# FascinationMachine.net
KiCad netlist of a schematic drawn in EAGLE
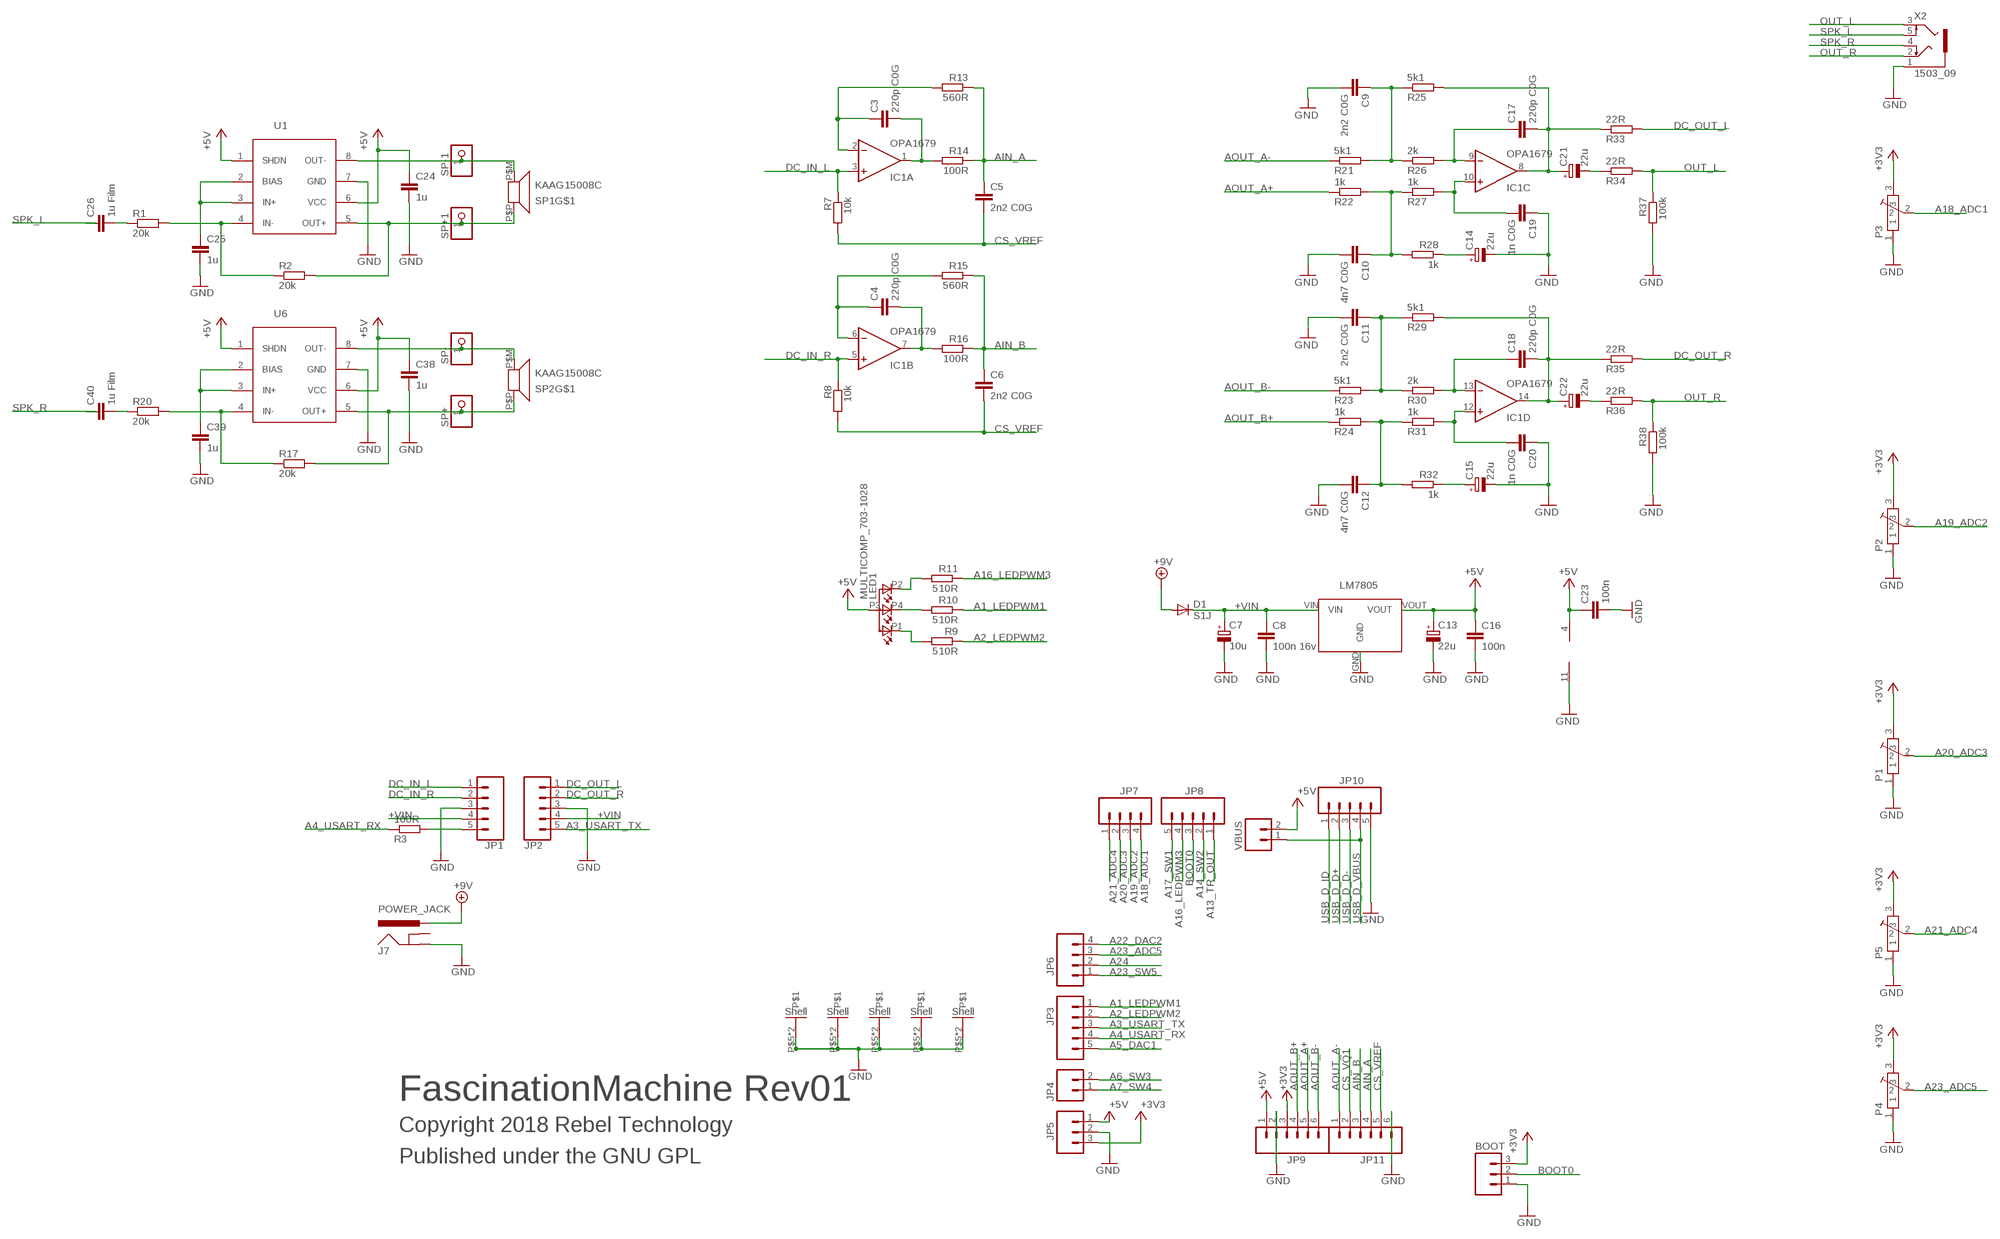
[diagram p0: schematic, sheet 1]

(export (version "E")
  (design (tool "Eeschema 10.0.6"))
  (components
    (comp (ref "BOOT")
      (value "M03PTH")
      (footprint "eagle-import:1X03")
      (libsource (lib "eagle-import") (part "M03PTH"))
    )
    (comp (ref "C3")
      (value "220p C0G")
      (footprint "eagle-import:C0603")
      (libsource (lib "eagle-import") (part "resistor_C-EUC0603"))
    )
    (comp (ref "C4")
      (value "220p C0G")
      (footprint "eagle-import:C0603")
      (libsource (lib "eagle-import") (part "resistor_C-EUC0603"))
    )
    (comp (ref "C5")
      (value "2n2 C0G")
      (footprint "eagle-import:C0603")
      (libsource (lib "eagle-import") (part "resistor_C-EUC0603"))
    )
    (comp (ref "C6")
      (value "2n2 C0G")
      (footprint "eagle-import:C0603")
      (libsource (lib "eagle-import") (part "resistor_C-EUC0603"))
    )
    (comp (ref "C7")
      (value "10u")
      (footprint "eagle-import:153CLV-0405")
      (libsource (lib "eagle-import") (part "CPOL-EU153CLV-0405"))
    )
    (comp (ref "C8")
      (value "100n 16v")
      (footprint "eagle-import:C0603")
      (libsource (lib "eagle-import") (part "C-EUC0603"))
    )
    (comp (ref "C9")
      (value "2n2 C0G")
      (footprint "eagle-import:C0603")
      (libsource (lib "eagle-import") (part "resistor_C-EUC0603"))
    )
    (comp (ref "C10")
      (value "4n7 C0G")
      (footprint "eagle-import:C0603")
      (libsource (lib "eagle-import") (part "resistor_C-EUC0603"))
    )
    (comp (ref "C11")
      (value "2n2 C0G")
      (footprint "eagle-import:C0603")
      (libsource (lib "eagle-import") (part "resistor_C-EUC0603"))
    )
    (comp (ref "C12")
      (value "4n7 C0G")
      (footprint "eagle-import:C0603")
      (libsource (lib "eagle-import") (part "resistor_C-EUC0603"))
    )
    (comp (ref "C13")
      (value "22u")
      (footprint "eagle-import:CPOL-5")
      (libsource (lib "eagle-import") (part "CPOL-EU153CLV-0505"))
    )
    (comp (ref "C14")
      (value "22u")
      (footprint "eagle-import:CPOL-5")
      (libsource (lib "eagle-import") (part "CPOL-EU153CLV-0505"))
    )
    (comp (ref "C15")
      (value "22u")
      (footprint "eagle-import:CPOL-5")
      (libsource (lib "eagle-import") (part "CPOL-EU153CLV-0505"))
    )
    (comp (ref "C16")
      (value "100n")
      (footprint "eagle-import:C0603")
      (libsource (lib "eagle-import") (part "C-EUC0603"))
    )
    (comp (ref "C17")
      (value "220p C0G")
      (footprint "eagle-import:C0603")
      (libsource (lib "eagle-import") (part "resistor_C-EUC0603"))
    )
    (comp (ref "C18")
      (value "220p C0G")
      (footprint "eagle-import:C0603")
      (libsource (lib "eagle-import") (part "resistor_C-EUC0603"))
    )
    (comp (ref "C19")
      (value "1n C0G")
      (footprint "eagle-import:C0603")
      (libsource (lib "eagle-import") (part "resistor_C-EUC0603"))
    )
    (comp (ref "C20")
      (value "1n C0G")
      (footprint "eagle-import:C0603")
      (libsource (lib "eagle-import") (part "resistor_C-EUC0603"))
    )
    (comp (ref "C21")
      (value "22u")
      (footprint "eagle-import:CPOL-5")
      (libsource (lib "eagle-import") (part "CPOL-EU153CLV-0505"))
    )
    (comp (ref "C22")
      (value "22u")
      (footprint "eagle-import:CPOL-5")
      (libsource (lib "eagle-import") (part "CPOL-EU153CLV-0505"))
    )
    (comp (ref "C23")
      (value "100n")
      (footprint "eagle-import:C0603")
      (libsource (lib "eagle-import") (part "resistor_C-EUC0603"))
    )
    (comp (ref "C24")
      (value "1u")
      (footprint "eagle-import:C0603")
      (libsource (lib "eagle-import") (part "resistor_348_C-EUC0603"))
    )
    (comp (ref "C25")
      (value "1u")
      (footprint "eagle-import:C0603")
      (libsource (lib "eagle-import") (part "resistor_348_C-EUC0603"))
    )
    (comp (ref "C26")
      (value "1u Film")
      (footprint "eagle-import:C1210")
      (libsource (lib "eagle-import") (part "C-EUC1210"))
    )
    (comp (ref "C38")
      (value "1u")
      (footprint "eagle-import:C0603")
      (libsource (lib "eagle-import") (part "resistor_348_C-EUC0603"))
    )
    (comp (ref "C39")
      (value "1u")
      (footprint "eagle-import:C0603")
      (libsource (lib "eagle-import") (part "resistor_348_C-EUC0603"))
    )
    (comp (ref "C40")
      (value "1u Film")
      (footprint "eagle-import:C1210")
      (libsource (lib "eagle-import") (part "C-EUC1210"))
    )
    (comp (ref "D1")
      (value "S1J")
      (footprint "eagle-import:SMA-DIODE")
      (libsource (lib "eagle-import") (part "DIODESMA"))
    )
    (comp (ref "IC1")
      (value "OPA1679")
      (footprint "eagle-import:SO14")
      (libsource (lib "eagle-import") (part "LM324D"))
    )
    (comp (ref "J7")
      (value "POWER_JACK")
      (footprint "eagle-import:DC_JACK_SLOT")
      (libsource (lib "eagle-import") (part "POWER_JACK"))
    )
    (comp (ref "JP1")
      (value "CONN_05JST-VERT")
      (footprint "eagle-import:JST-5-PTH-VERT")
      (libsource (lib "eagle-import") (part "CONN_05JST-VERT"))
    )
    (comp (ref "JP2")
      (value "CONN_05JST-VERT")
      (footprint "eagle-import:JST-5-PTH-VERT")
      (libsource (lib "eagle-import") (part "CONN_05JST-VERT"))
    )
    (comp (ref "JP3")
      (value "M05PTH")
      (footprint "eagle-import:1X05")
      (libsource (lib "eagle-import") (part "M05PTH"))
    )
    (comp (ref "JP4")
      (value "M02PTH")
      (footprint "eagle-import:1X02")
      (libsource (lib "eagle-import") (part "M02PTH"))
    )
    (comp (ref "JP5")
      (value "M03PTH")
      (footprint "eagle-import:1X03")
      (libsource (lib "eagle-import") (part "M03PTH"))
    )
    (comp (ref "JP6")
      (value "M04PTH")
      (footprint "eagle-import:1X04")
      (libsource (lib "eagle-import") (part "M04PTH"))
    )
    (comp (ref "JP7")
      (value "M04PTH")
      (footprint "eagle-import:1X04")
      (libsource (lib "eagle-import") (part "M04PTH"))
    )
    (comp (ref "JP8")
      (value "M05PTH")
      (footprint "eagle-import:1X05")
      (libsource (lib "eagle-import") (part "M05PTH"))
    )
    (comp (ref "JP9")
      (value "M06SIP")
      (footprint "eagle-import:1X06")
      (libsource (lib "eagle-import") (part "M06SIP"))
    )
    (comp (ref "JP10")
      (value "M05PTH")
      (footprint "eagle-import:1X05")
      (libsource (lib "eagle-import") (part "M05PTH"))
    )
    (comp (ref "JP11")
      (value "M06SIP")
      (footprint "eagle-import:1X06")
      (libsource (lib "eagle-import") (part "M06SIP"))
    )
    (comp (ref "LED1")
      (value "MULTICOMP_703-1028")
      (footprint "eagle-import:RGB-LED-703-1028")
      (libsource (lib "eagle-import") (part "MULTICOMP_703-1028"))
    )
    (comp (ref "P1")
      (value "POT-ALPS-RK09L1140")
      (footprint "eagle-import:POT-ALPS-RK09L1140")
      (libsource (lib "eagle-import") (part "POT-ALPS-RK09L1140"))
    )
    (comp (ref "P2")
      (value "POT-ALPS-RK09L1140")
      (footprint "eagle-import:POT-ALPS-RK09L1140")
      (libsource (lib "eagle-import") (part "POT-ALPS-RK09L1140"))
    )
    (comp (ref "P3")
      (value "POT-ALPS-RK09L1140")
      (footprint "eagle-import:POT-ALPS-RK09L1140")
      (libsource (lib "eagle-import") (part "POT-ALPS-RK09L1140"))
    )
    (comp (ref "P4")
      (value "POT-ALPS-RK09L1140")
      (footprint "eagle-import:POT-ALPS-RK09L1140")
      (libsource (lib "eagle-import") (part "POT-ALPS-RK09L1140"))
    )
    (comp (ref "P5")
      (value "POT-ALPS-RK09L1140")
      (footprint "eagle-import:POT-ALPS-RK09L1140")
      (libsource (lib "eagle-import") (part "POT-ALPS-RK09L1140"))
    )
    (comp (ref "R1")
      (value "20k")
      (footprint "eagle-import:0603")
      (libsource (lib "eagle-import") (part "R-EU_0603"))
    )
    (comp (ref "R2")
      (value "20k")
      (footprint "eagle-import:0603")
      (libsource (lib "eagle-import") (part "R-EU_0603"))
    )
    (comp (ref "R3")
      (value "100R")
      (footprint "eagle-import:0603")
      (libsource (lib "eagle-import") (part "R-EU_0603"))
    )
    (comp (ref "R7")
      (value "10k")
      (footprint "eagle-import:0603")
      (libsource (lib "eagle-import") (part "R-EU_0603"))
    )
    (comp (ref "R8")
      (value "10k")
      (footprint "eagle-import:0603")
      (libsource (lib "eagle-import") (part "R-EU_0603"))
    )
    (comp (ref "R9")
      (value "510R")
      (footprint "eagle-import:0603")
      (libsource (lib "eagle-import") (part "R-EU_0603"))
    )
    (comp (ref "R10")
      (value "510R")
      (footprint "eagle-import:0603")
      (libsource (lib "eagle-import") (part "R-EU_0603"))
    )
    (comp (ref "R11")
      (value "510R")
      (footprint "eagle-import:0603")
      (libsource (lib "eagle-import") (part "R-EU_0603"))
    )
    (comp (ref "R13")
      (value "560R")
      (footprint "eagle-import:0603")
      (libsource (lib "eagle-import") (part "R-EU_0603"))
    )
    (comp (ref "R14")
      (value "100R")
      (footprint "eagle-import:0603")
      (libsource (lib "eagle-import") (part "R-EU_0603"))
    )
    (comp (ref "R15")
      (value "560R")
      (footprint "eagle-import:0603")
      (libsource (lib "eagle-import") (part "R-EU_0603"))
    )
    (comp (ref "R16")
      (value "100R")
      (footprint "eagle-import:0603")
      (libsource (lib "eagle-import") (part "R-EU_0603"))
    )
    (comp (ref "R17")
      (value "20k")
      (footprint "eagle-import:0603")
      (libsource (lib "eagle-import") (part "R-EU_0603"))
    )
    (comp (ref "R20")
      (value "20k")
      (footprint "eagle-import:0603")
      (libsource (lib "eagle-import") (part "R-EU_0603"))
    )
    (comp (ref "R21")
      (value "5k1")
      (footprint "eagle-import:0603")
      (libsource (lib "eagle-import") (part "R-EU_0603"))
    )
    (comp (ref "R22")
      (value "1k")
      (footprint "eagle-import:0603")
      (libsource (lib "eagle-import") (part "R-EU_0603"))
    )
    (comp (ref "R23")
      (value "5k1")
      (footprint "eagle-import:0603")
      (libsource (lib "eagle-import") (part "R-EU_0603"))
    )
    (comp (ref "R24")
      (value "1k")
      (footprint "eagle-import:0603")
      (libsource (lib "eagle-import") (part "R-EU_0603"))
    )
    (comp (ref "R25")
      (value "5k1")
      (footprint "eagle-import:0603")
      (libsource (lib "eagle-import") (part "R-EU_0603"))
    )
    (comp (ref "R26")
      (value "2k")
      (footprint "eagle-import:0603")
      (libsource (lib "eagle-import") (part "R-EU_0603"))
    )
    (comp (ref "R27")
      (value "1k")
      (footprint "eagle-import:0603")
      (libsource (lib "eagle-import") (part "R-EU_0603"))
    )
    (comp (ref "R28")
      (value "1k")
      (footprint "eagle-import:0603")
      (libsource (lib "eagle-import") (part "R-EU_0603"))
    )
    (comp (ref "R29")
      (value "5k1")
      (footprint "eagle-import:0603")
      (libsource (lib "eagle-import") (part "R-EU_0603"))
    )
    (comp (ref "R30")
      (value "2k")
      (footprint "eagle-import:0603")
      (libsource (lib "eagle-import") (part "R-EU_0603"))
    )
    (comp (ref "R31")
      (value "1k")
      (footprint "eagle-import:0603")
      (libsource (lib "eagle-import") (part "R-EU_0603"))
    )
    (comp (ref "R32")
      (value "1k")
      (footprint "eagle-import:0603")
      (libsource (lib "eagle-import") (part "R-EU_0603"))
    )
    (comp (ref "R33")
      (value "22R")
      (footprint "eagle-import:0603")
      (libsource (lib "eagle-import") (part "R-EU_0603"))
    )
    (comp (ref "R34")
      (value "22R")
      (footprint "eagle-import:0603")
      (libsource (lib "eagle-import") (part "R-EU_0603"))
    )
    (comp (ref "R35")
      (value "22R")
      (footprint "eagle-import:0603")
      (libsource (lib "eagle-import") (part "R-EU_0603"))
    )
    (comp (ref "R36")
      (value "22R")
      (footprint "eagle-import:0603")
      (libsource (lib "eagle-import") (part "R-EU_0603"))
    )
    (comp (ref "R37")
      (value "100k")
      (footprint "eagle-import:0603")
      (libsource (lib "eagle-import") (part "R-EU_0603"))
    )
    (comp (ref "R38")
      (value "100k")
      (footprint "eagle-import:0603")
      (libsource (lib "eagle-import") (part "R-EU_0603"))
    )
    (comp (ref "SP+")
      (value "PINHD-1X1")
      (footprint "eagle-import:1X01")
      (libsource (lib "eagle-import") (part "PINHD-1X1"))
    )
    (comp (ref "SP+1")
      (value "PINHD-1X1")
      (footprint "eagle-import:1X01")
      (libsource (lib "eagle-import") (part "PINHD-1X1"))
    )
    (comp (ref "SP-")
      (value "PINHD-1X1")
      (footprint "eagle-import:1X01")
      (libsource (lib "eagle-import") (part "PINHD-1X1"))
    )
    (comp (ref "SP-1")
      (value "PINHD-1X1")
      (footprint "eagle-import:1X01")
      (libsource (lib "eagle-import") (part "PINHD-1X1"))
    )
    (comp (ref "SP1")
      (value "KAAG15008C")
      (footprint "eagle-import:KAAG15008C")
      (libsource (lib "eagle-import") (part "KAAG15008C"))
    )
    (comp (ref "SP2")
      (value "KAAG15008C")
      (footprint "eagle-import:KAAG15008C")
      (libsource (lib "eagle-import") (part "KAAG15008C"))
    )
    (comp (ref "U1")
      (value "MAX9716")
      (footprint "eagle-import:UMAX8-THERMAL")
      (libsource (lib "eagle-import") (part "MAX9716"))
    )
    (comp (ref "U2")
      (value "LM7805")
      (footprint "eagle-import:REG_S9V11F5")
      (libsource (lib "eagle-import") (part "REG_S9V11F5"))
    )
    (comp (ref "U6")
      (value "MAX9716")
      (footprint "eagle-import:UMAX8-THERMAL")
      (libsource (lib "eagle-import") (part "MAX9716"))
    )
    (comp (ref "VBUS")
      (value "M02PTH")
      (footprint "eagle-import:1X02")
      (libsource (lib "eagle-import") (part "M02PTH"))
    )
    (comp (ref "X2")
      (value "1503_09")
      (footprint "eagle-import:1503_09")
      (libsource (lib "eagle-import") (part "1503_09"))
    )
  )
  (nets
    (net (code "1") (name "+3V3") (class "Default")
      (node (ref "BOOT") (pin "3") (pinfunction "3_3") (pintype "passive"))
      (node (ref "JP5") (pin "3") (pinfunction "3_3") (pintype "passive"))
      (node (ref "JP9") (pin "3") (pinfunction "3_3") (pintype "passive"))
      (node (ref "P1") (pin "3") (pinfunction "3_3") (pintype "bidirectional"))
      (node (ref "P2") (pin "3") (pinfunction "3_3") (pintype "bidirectional"))
      (node (ref "P3") (pin "3") (pinfunction "3_3") (pintype "bidirectional"))
      (node (ref "P4") (pin "3") (pinfunction "3_3") (pintype "bidirectional"))
      (node (ref "P5") (pin "3") (pinfunction "3_3") (pintype "bidirectional"))
    )
    (net (code "2") (name "+5V") (class "Default")
      (node (ref "C13") (pin "+") (pinfunction "+_+") (pintype "passive"))
      (node (ref "C16") (pin "1") (pinfunction "1_1") (pintype "passive"))
      (node (ref "C23") (pin "1") (pinfunction "1_1") (pintype "passive"))
      (node (ref "C24") (pin "1") (pinfunction "1_1") (pintype "passive"))
      (node (ref "C38") (pin "1") (pinfunction "1_1") (pintype "passive"))
      (node (ref "IC1") (pin "4") (pinfunction "V+_4") (pintype "power_in"))
      (node (ref "JP5") (pin "1") (pinfunction "1_1") (pintype "passive"))
      (node (ref "JP9") (pin "1") (pinfunction "1_1") (pintype "passive"))
      (node (ref "LED1") (pin "P3") (pinfunction "A_P3") (pintype "passive"))
      (node (ref "U1") (pin "1") (pinfunction "SHDN_1") (pintype "bidirectional"))
      (node (ref "U1") (pin "6") (pinfunction "VCC_6") (pintype "bidirectional"))
      (node (ref "U2") (pin "VOUT") (pinfunction "VOUT_VOUT") (pintype "output"))
      (node (ref "U6") (pin "1") (pinfunction "SHDN_1") (pintype "bidirectional"))
      (node (ref "U6") (pin "6") (pinfunction "VCC_6") (pintype "bidirectional"))
      (node (ref "VBUS") (pin "2") (pinfunction "2_2") (pintype "passive"))
    )
    (net (code "3") (name "+9V") (class "Default")
      (node (ref "D1") (pin "A") (pinfunction "A_A") (pintype "passive"))
      (node (ref "J7") (pin "PWR") (pinfunction "PWR_PWR") (pintype "bidirectional"))
    )
    (net (code "4") (name "/+VIN") (class "Default")
      (node (ref "C7") (pin "+") (pinfunction "+_+") (pintype "passive"))
      (node (ref "C8") (pin "1") (pinfunction "1_1") (pintype "passive"))
      (node (ref "D1") (pin "C") (pinfunction "C_C") (pintype "passive"))
      (node (ref "JP1") (pin "4") (pinfunction "4_4") (pintype "passive"))
      (node (ref "JP2") (pin "4") (pinfunction "4_4") (pintype "passive"))
      (node (ref "U2") (pin "VIN") (pinfunction "VIN_VIN") (pintype "input"))
    )
    (net (code "5") (name "/A1_LEDPWM1") (class "Default")
      (node (ref "JP3") (pin "1") (pinfunction "1_1") (pintype "passive"))
      (node (ref "R10") (pin "1") (pinfunction "1_1") (pintype "passive"))
    )
    (net (code "6") (name "/A2_LEDPWM2") (class "Default")
      (node (ref "JP3") (pin "2") (pinfunction "2_2") (pintype "passive"))
      (node (ref "R9") (pin "1") (pinfunction "1_1") (pintype "passive"))
    )
    (net (code "7") (name "/A3_USART_TX") (class "Default")
      (node (ref "JP2") (pin "5") (pinfunction "5_5") (pintype "passive"))
      (node (ref "JP3") (pin "3") (pinfunction "3_3") (pintype "passive"))
    )
    (net (code "8") (name "/A4_USART_RX") (class "Default")
      (node (ref "JP3") (pin "4") (pinfunction "4_4") (pintype "passive"))
      (node (ref "R3") (pin "1") (pinfunction "1_1") (pintype "passive"))
    )
    (net (code "9") (name "/A5_DAC1") (class "Default")
      (node (ref "JP3") (pin "5") (pinfunction "5_5") (pintype "passive"))
    )
    (net (code "10") (name "/A6_SW3") (class "Default")
      (node (ref "JP4") (pin "2") (pinfunction "2_2") (pintype "passive"))
    )
    (net (code "11") (name "/A7_SW4") (class "Default")
      (node (ref "JP4") (pin "1") (pinfunction "1_1") (pintype "passive"))
    )
    (net (code "12") (name "/A13_TR_OUT") (class "Default")
      (node (ref "JP8") (pin "1") (pinfunction "1_1") (pintype "passive"))
    )
    (net (code "13") (name "/A14_SW2") (class "Default")
      (node (ref "JP8") (pin "2") (pinfunction "2_2") (pintype "passive"))
    )
    (net (code "14") (name "/A16_LEDPWM3") (class "Default")
      (node (ref "JP8") (pin "4") (pinfunction "4_4") (pintype "passive"))
      (node (ref "R11") (pin "1") (pinfunction "1_1") (pintype "passive"))
    )
    (net (code "15") (name "/A17_SW1") (class "Default")
      (node (ref "JP8") (pin "5") (pinfunction "5_5") (pintype "passive"))
    )
    (net (code "16") (name "/A18_ADC1") (class "Default")
      (node (ref "JP7") (pin "4") (pinfunction "4_4") (pintype "passive"))
      (node (ref "P3") (pin "2") (pinfunction "2_2") (pintype "bidirectional"))
    )
    (net (code "17") (name "/A19_ADC2") (class "Default")
      (node (ref "JP7") (pin "3") (pinfunction "3_3") (pintype "passive"))
      (node (ref "P2") (pin "2") (pinfunction "2_2") (pintype "bidirectional"))
    )
    (net (code "18") (name "/A20_ADC3") (class "Default")
      (node (ref "JP7") (pin "2") (pinfunction "2_2") (pintype "passive"))
      (node (ref "P1") (pin "2") (pinfunction "2_2") (pintype "bidirectional"))
    )
    (net (code "19") (name "/A21_ADC4") (class "Default")
      (node (ref "JP7") (pin "1") (pinfunction "1_1") (pintype "passive"))
      (node (ref "P5") (pin "2") (pinfunction "2_2") (pintype "bidirectional"))
    )
    (net (code "20") (name "/A22_DAC2") (class "Default")
      (node (ref "JP6") (pin "4") (pinfunction "4_4") (pintype "passive"))
    )
    (net (code "21") (name "/A23_ADC5") (class "Default")
      (node (ref "JP6") (pin "3") (pinfunction "3_3") (pintype "passive"))
      (node (ref "P4") (pin "2") (pinfunction "2_2") (pintype "bidirectional"))
    )
    (net (code "22") (name "/A23_SW5") (class "Default")
      (node (ref "JP6") (pin "1") (pinfunction "1_1") (pintype "passive"))
    )
    (net (code "23") (name "/A24") (class "Default")
      (node (ref "JP6") (pin "2") (pinfunction "2_2") (pintype "passive"))
    )
    (net (code "24") (name "/AIN_A") (class "Default")
      (node (ref "C5") (pin "1") (pinfunction "1_1") (pintype "passive"))
      (node (ref "JP11") (pin "4") (pinfunction "4_4") (pintype "passive"))
      (node (ref "R13") (pin "1") (pinfunction "1_1") (pintype "passive"))
      (node (ref "R14") (pin "1") (pinfunction "1_1") (pintype "passive"))
    )
    (net (code "25") (name "/AIN_B") (class "Default")
      (node (ref "C6") (pin "1") (pinfunction "1_1") (pintype "passive"))
      (node (ref "JP11") (pin "3") (pinfunction "3_3") (pintype "passive"))
      (node (ref "R15") (pin "1") (pinfunction "1_1") (pintype "passive"))
      (node (ref "R16") (pin "1") (pinfunction "1_1") (pintype "passive"))
    )
    (net (code "26") (name "/AOUT_A+") (class "Default")
      (node (ref "JP9") (pin "5") (pinfunction "5_5") (pintype "passive"))
      (node (ref "R22") (pin "1") (pinfunction "1_1") (pintype "passive"))
    )
    (net (code "27") (name "/AOUT_A-") (class "Default")
      (node (ref "JP11") (pin "1") (pinfunction "1_1") (pintype "passive"))
      (node (ref "R21") (pin "1") (pinfunction "1_1") (pintype "passive"))
    )
    (net (code "28") (name "/AOUT_B+") (class "Default")
      (node (ref "JP9") (pin "4") (pinfunction "4_4") (pintype "passive"))
      (node (ref "R24") (pin "1") (pinfunction "1_1") (pintype "passive"))
    )
    (net (code "29") (name "/AOUT_B-") (class "Default")
      (node (ref "JP9") (pin "6") (pinfunction "6_6") (pintype "passive"))
      (node (ref "R23") (pin "1") (pinfunction "1_1") (pintype "passive"))
    )
    (net (code "30") (name "/BOOT0") (class "Default")
      (node (ref "BOOT") (pin "2") (pinfunction "2_2") (pintype "passive"))
      (node (ref "JP8") (pin "3") (pinfunction "3_3") (pintype "passive"))
    )
    (net (code "31") (name "/CS_VQ1") (class "Default")
      (node (ref "JP11") (pin "2") (pinfunction "2_2") (pintype "passive"))
    )
    (net (code "32") (name "/CS_VREF") (class "Default")
      (node (ref "C5") (pin "2") (pinfunction "2_2") (pintype "passive"))
      (node (ref "C6") (pin "2") (pinfunction "2_2") (pintype "passive"))
      (node (ref "JP11") (pin "5") (pinfunction "5_5") (pintype "passive"))
      (node (ref "R7") (pin "2") (pinfunction "2_2") (pintype "passive"))
      (node (ref "R8") (pin "2") (pinfunction "2_2") (pintype "passive"))
    )
    (net (code "33") (name "/DC_IN_L") (class "Default")
      (node (ref "IC1") (pin "3") (pinfunction "+IN_3") (pintype "input"))
      (node (ref "JP1") (pin "1") (pinfunction "1_1") (pintype "passive"))
      (node (ref "R7") (pin "1") (pinfunction "1_1") (pintype "passive"))
    )
    (net (code "34") (name "/DC_IN_R") (class "Default")
      (node (ref "IC1") (pin "5") (pinfunction "+IN_5") (pintype "input"))
      (node (ref "JP1") (pin "2") (pinfunction "2_2") (pintype "passive"))
      (node (ref "R8") (pin "1") (pinfunction "1_1") (pintype "passive"))
    )
    (net (code "35") (name "/DC_OUT_L") (class "Default")
      (node (ref "JP2") (pin "1") (pinfunction "1_1") (pintype "passive"))
      (node (ref "R33") (pin "2") (pinfunction "2_2") (pintype "passive"))
    )
    (net (code "36") (name "/DC_OUT_R") (class "Default")
      (node (ref "JP2") (pin "2") (pinfunction "2_2") (pintype "passive"))
      (node (ref "R35") (pin "2") (pinfunction "2_2") (pintype "passive"))
    )
    (net (code "37") (name "/OUT_L") (class "Default")
      (node (ref "R34") (pin "2") (pinfunction "2_2") (pintype "passive"))
      (node (ref "R37") (pin "1") (pinfunction "1_1") (pintype "passive"))
      (node (ref "X2") (pin "3") (pinfunction "3_3") (pintype "passive"))
    )
    (net (code "38") (name "/OUT_R") (class "Default")
      (node (ref "R36") (pin "2") (pinfunction "2_2") (pintype "passive"))
      (node (ref "R38") (pin "1") (pinfunction "1_1") (pintype "passive"))
      (node (ref "X2") (pin "2") (pinfunction "2_2") (pintype "passive"))
    )
    (net (code "39") (name "/SPK_L") (class "Default")
      (node (ref "C26") (pin "1") (pinfunction "1_1") (pintype "passive"))
      (node (ref "X2") (pin "5") (pinfunction "5_5") (pintype "passive"))
    )
    (net (code "40") (name "/SPK_R") (class "Default")
      (node (ref "C40") (pin "1") (pinfunction "1_1") (pintype "passive"))
      (node (ref "X2") (pin "4") (pinfunction "4_4") (pintype "passive"))
    )
    (net (code "41") (name "/USB_D_D+") (class "Default")
      (node (ref "JP10") (pin "2") (pinfunction "2_2") (pintype "passive"))
    )
    (net (code "42") (name "/USB_D_D-") (class "Default")
      (node (ref "JP10") (pin "3") (pinfunction "3_3") (pintype "passive"))
    )
    (net (code "43") (name "/USB_D_ID") (class "Default")
      (node (ref "JP10") (pin "1") (pinfunction "1_1") (pintype "passive"))
    )
    (net (code "44") (name "/USB_D_VBUS") (class "Default")
      (node (ref "JP10") (pin "4") (pinfunction "4_4") (pintype "passive"))
      (node (ref "VBUS") (pin "1") (pinfunction "1_1") (pintype "passive"))
    )
    (net (code "45") (name "GND") (class "Default")
      (node (ref "BOOT") (pin "1") (pinfunction "1_1") (pintype "passive"))
      (node (ref "C10") (pin "2") (pinfunction "2_2") (pintype "passive"))
      (node (ref "C11") (pin "2") (pinfunction "2_2") (pintype "passive"))
      (node (ref "C12") (pin "2") (pinfunction "2_2") (pintype "passive"))
      (node (ref "C13") (pin "-") (pinfunction "-_-") (pintype "passive"))
      (node (ref "C14") (pin "-") (pinfunction "-_-") (pintype "passive"))
      (node (ref "C15") (pin "-") (pinfunction "-_-") (pintype "passive"))
      (node (ref "C16") (pin "2") (pinfunction "2_2") (pintype "passive"))
      (node (ref "C19") (pin "1") (pinfunction "1_1") (pintype "passive"))
      (node (ref "C20") (pin "1") (pinfunction "1_1") (pintype "passive"))
      (node (ref "C23") (pin "2") (pinfunction "2_2") (pintype "passive"))
      (node (ref "C24") (pin "2") (pinfunction "2_2") (pintype "passive"))
      (node (ref "C25") (pin "2") (pinfunction "2_2") (pintype "passive"))
      (node (ref "C38") (pin "2") (pinfunction "2_2") (pintype "passive"))
      (node (ref "C39") (pin "2") (pinfunction "2_2") (pintype "passive"))
      (node (ref "C7") (pin "-") (pinfunction "-_-") (pintype "passive"))
      (node (ref "C8") (pin "2") (pinfunction "2_2") (pintype "passive"))
      (node (ref "C9") (pin "2") (pinfunction "2_2") (pintype "passive"))
      (node (ref "IC1") (pin "11") (pinfunction "V-_11") (pintype "power_in"))
      (node (ref "J7") (pin "GND") (pinfunction "GND_GND") (pintype "bidirectional"))
      (node (ref "JP1") (pin "3") (pinfunction "3_3") (pintype "passive"))
      (node (ref "JP10") (pin "5") (pinfunction "5_5") (pintype "passive"))
      (node (ref "JP11") (pin "6") (pinfunction "6_6") (pintype "passive"))
      (node (ref "JP2") (pin "3") (pinfunction "3_3") (pintype "passive"))
      (node (ref "JP5") (pin "2") (pinfunction "2_2") (pintype "passive"))
      (node (ref "JP9") (pin "2") (pinfunction "2_2") (pintype "passive"))
      (node (ref "P1") (pin "1") (pinfunction "1_1") (pintype "bidirectional"))
      (node (ref "P1") (pin "P$5") (pinfunction "P$1_P$5") (pintype "bidirectional"))
      (node (ref "P1") (pin "P$6") (pinfunction "P$1_P$6") (pintype "bidirectional"))
      (node (ref "P2") (pin "1") (pinfunction "1_1") (pintype "bidirectional"))
      (node (ref "P2") (pin "P$5") (pinfunction "P$1_P$5") (pintype "bidirectional"))
      (node (ref "P2") (pin "P$6") (pinfunction "P$1_P$6") (pintype "bidirectional"))
      (node (ref "P3") (pin "1") (pinfunction "1_1") (pintype "bidirectional"))
      (node (ref "P3") (pin "P$5") (pinfunction "P$1_P$5") (pintype "bidirectional"))
      (node (ref "P3") (pin "P$6") (pinfunction "P$1_P$6") (pintype "bidirectional"))
      (node (ref "P4") (pin "1") (pinfunction "1_1") (pintype "bidirectional"))
      (node (ref "P4") (pin "P$5") (pinfunction "P$1_P$5") (pintype "bidirectional"))
      (node (ref "P4") (pin "P$6") (pinfunction "P$1_P$6") (pintype "bidirectional"))
      (node (ref "P5") (pin "1") (pinfunction "1_1") (pintype "bidirectional"))
      (node (ref "P5") (pin "P$5") (pinfunction "P$1_P$5") (pintype "bidirectional"))
      (node (ref "P5") (pin "P$6") (pinfunction "P$1_P$6") (pintype "bidirectional"))
      (node (ref "R37") (pin "2") (pinfunction "2_2") (pintype "passive"))
      (node (ref "R38") (pin "2") (pinfunction "2_2") (pintype "passive"))
      (node (ref "U1") (pin "7") (pinfunction "GND_7") (pintype "bidirectional"))
      (node (ref "U2") (pin "GND") (pinfunction "GND_GND") (pintype "power_in"))
      (node (ref "U6") (pin "7") (pinfunction "GND_7") (pintype "bidirectional"))
      (node (ref "X2") (pin "1") (pinfunction "1_1") (pintype "passive"))
    )
    (net (code "46") (name "Net-(C9-Pad1)") (class "Default")
      (node (ref "C9") (pin "1") (pinfunction "1_1") (pintype "passive"))
      (node (ref "R21") (pin "2") (pinfunction "2_2") (pintype "passive"))
      (node (ref "R25") (pin "1") (pinfunction "1_1") (pintype "passive"))
      (node (ref "R26") (pin "1") (pinfunction "1_1") (pintype "passive"))
    )
    (net (code "47") (name "Net-(C10-Pad1)") (class "Default")
      (node (ref "C10") (pin "1") (pinfunction "1_1") (pintype "passive"))
      (node (ref "R22") (pin "2") (pinfunction "2_2") (pintype "passive"))
      (node (ref "R27") (pin "1") (pinfunction "1_1") (pintype "passive"))
      (node (ref "R28") (pin "2") (pinfunction "2_2") (pintype "passive"))
    )
    (net (code "48") (name "Net-(C11-Pad1)") (class "Default")
      (node (ref "C11") (pin "1") (pinfunction "1_1") (pintype "passive"))
      (node (ref "R23") (pin "2") (pinfunction "2_2") (pintype "passive"))
      (node (ref "R29") (pin "1") (pinfunction "1_1") (pintype "passive"))
      (node (ref "R30") (pin "1") (pinfunction "1_1") (pintype "passive"))
    )
    (net (code "49") (name "Net-(C12-Pad1)") (class "Default")
      (node (ref "C12") (pin "1") (pinfunction "1_1") (pintype "passive"))
      (node (ref "R24") (pin "2") (pinfunction "2_2") (pintype "passive"))
      (node (ref "R31") (pin "1") (pinfunction "1_1") (pintype "passive"))
      (node (ref "R32") (pin "2") (pinfunction "2_2") (pintype "passive"))
    )
    (net (code "50") (name "Net-(C14-Pad+)") (class "Default")
      (node (ref "C14") (pin "+") (pinfunction "+_+") (pintype "passive"))
      (node (ref "R28") (pin "1") (pinfunction "1_1") (pintype "passive"))
    )
    (net (code "51") (name "Net-(C15-Pad+)") (class "Default")
      (node (ref "C15") (pin "+") (pinfunction "+_+") (pintype "passive"))
      (node (ref "R32") (pin "1") (pinfunction "1_1") (pintype "passive"))
    )
    (net (code "52") (name "Net-(C21-Pad-)") (class "Default")
      (node (ref "C21") (pin "-") (pinfunction "-_-") (pintype "passive"))
      (node (ref "R34") (pin "1") (pinfunction "1_1") (pintype "passive"))
    )
    (net (code "53") (name "Net-(C22-Pad-)") (class "Default")
      (node (ref "C22") (pin "-") (pinfunction "-_-") (pintype "passive"))
      (node (ref "R36") (pin "1") (pinfunction "1_1") (pintype "passive"))
    )
    (net (code "54") (name "Net-(C26-Pad2)") (class "Default")
      (node (ref "C26") (pin "2") (pinfunction "2_2") (pintype "passive"))
      (node (ref "R1") (pin "1") (pinfunction "1_1") (pintype "passive"))
    )
    (net (code "55") (name "Net-(C40-Pad2)") (class "Default")
      (node (ref "C40") (pin "2") (pinfunction "2_2") (pintype "passive"))
      (node (ref "R20") (pin "1") (pinfunction "1_1") (pintype "passive"))
    )
    (net (code "56") (name "Net-(IC1A--IN)") (class "Default")
      (node (ref "C3") (pin "1") (pinfunction "1_1") (pintype "passive"))
      (node (ref "IC1") (pin "2") (pinfunction "-IN_2") (pintype "input"))
      (node (ref "R13") (pin "2") (pinfunction "2_2") (pintype "passive"))
    )
    (net (code "57") (name "Net-(IC1A-OUT)") (class "Default")
      (node (ref "C3") (pin "2") (pinfunction "2_2") (pintype "passive"))
      (node (ref "IC1") (pin "1") (pinfunction "OUT_1") (pintype "output"))
      (node (ref "R14") (pin "2") (pinfunction "2_2") (pintype "passive"))
    )
    (net (code "58") (name "Net-(IC1B--IN)") (class "Default")
      (node (ref "C4") (pin "1") (pinfunction "1_1") (pintype "passive"))
      (node (ref "IC1") (pin "6") (pinfunction "-IN_6") (pintype "input"))
      (node (ref "R15") (pin "2") (pinfunction "2_2") (pintype "passive"))
    )
    (net (code "59") (name "Net-(IC1B-OUT)") (class "Default")
      (node (ref "C4") (pin "2") (pinfunction "2_2") (pintype "passive"))
      (node (ref "IC1") (pin "7") (pinfunction "OUT_7") (pintype "output"))
      (node (ref "R16") (pin "2") (pinfunction "2_2") (pintype "passive"))
    )
    (net (code "60") (name "Net-(IC1C-+IN)") (class "Default")
      (node (ref "C19") (pin "2") (pinfunction "2_2") (pintype "passive"))
      (node (ref "IC1") (pin "10") (pinfunction "+IN_10") (pintype "input"))
      (node (ref "R27") (pin "2") (pinfunction "2_2") (pintype "passive"))
    )
    (net (code "61") (name "Net-(IC1C--IN)") (class "Default")
      (node (ref "C17") (pin "1") (pinfunction "1_1") (pintype "passive"))
      (node (ref "IC1") (pin "9") (pinfunction "-IN_9") (pintype "input"))
      (node (ref "R26") (pin "2") (pinfunction "2_2") (pintype "passive"))
    )
    (net (code "62") (name "Net-(IC1C-OUT)") (class "Default")
      (node (ref "C17") (pin "2") (pinfunction "2_2") (pintype "passive"))
      (node (ref "C21") (pin "+") (pinfunction "+_+") (pintype "passive"))
      (node (ref "IC1") (pin "8") (pinfunction "OUT_8") (pintype "output"))
      (node (ref "R25") (pin "2") (pinfunction "2_2") (pintype "passive"))
      (node (ref "R33") (pin "1") (pinfunction "1_1") (pintype "passive"))
    )
    (net (code "63") (name "Net-(IC1D-+IN)") (class "Default")
      (node (ref "C20") (pin "2") (pinfunction "2_2") (pintype "passive"))
      (node (ref "IC1") (pin "12") (pinfunction "+IN_12") (pintype "input"))
      (node (ref "R31") (pin "2") (pinfunction "2_2") (pintype "passive"))
    )
    (net (code "64") (name "Net-(IC1D--IN)") (class "Default")
      (node (ref "C18") (pin "1") (pinfunction "1_1") (pintype "passive"))
      (node (ref "IC1") (pin "13") (pinfunction "-IN_13") (pintype "input"))
      (node (ref "R30") (pin "2") (pinfunction "2_2") (pintype "passive"))
    )
    (net (code "65") (name "Net-(IC1D-OUT)") (class "Default")
      (node (ref "C18") (pin "2") (pinfunction "2_2") (pintype "passive"))
      (node (ref "C22") (pin "+") (pinfunction "+_+") (pintype "passive"))
      (node (ref "IC1") (pin "14") (pinfunction "OUT_14") (pintype "output"))
      (node (ref "R29") (pin "2") (pinfunction "2_2") (pintype "passive"))
      (node (ref "R35") (pin "1") (pinfunction "1_1") (pintype "passive"))
    )
    (net (code "66") (name "Net-(JP1-Pad5)") (class "Default")
      (node (ref "JP1") (pin "5") (pinfunction "5_5") (pintype "passive"))
      (node (ref "R3") (pin "2") (pinfunction "2_2") (pintype "passive"))
    )
    (net (code "67") (name "Net-(LED1-CBLUE)") (class "Default")
      (node (ref "LED1") (pin "P4") (pinfunction "CBLUE_P4") (pintype "passive"))
      (node (ref "R10") (pin "2") (pinfunction "2_2") (pintype "passive"))
    )
    (net (code "68") (name "Net-(LED1-CGREEN)") (class "Default")
      (node (ref "LED1") (pin "P2") (pinfunction "CGREEN_P2") (pintype "passive"))
      (node (ref "R11") (pin "2") (pinfunction "2_2") (pintype "passive"))
    )
    (net (code "69") (name "Net-(LED1-CRED)") (class "Default")
      (node (ref "LED1") (pin "P1") (pinfunction "CRED_P1") (pintype "passive"))
      (node (ref "R9") (pin "2") (pinfunction "2_2") (pintype "passive"))
    )
    (net (code "70") (name "Net-(SP1A-1)") (class "Default")
      (node (ref "R2") (pin "2") (pinfunction "2_2") (pintype "passive"))
      (node (ref "SP+1") (pin "1") (pinfunction "1_1") (pintype "passive"))
      (node (ref "SP1") (pin "P$P") (pinfunction "1_P$P") (pintype "passive"))
      (node (ref "U1") (pin "5") (pinfunction "OUT+_5") (pintype "bidirectional"))
    )
    (net (code "71") (name "Net-(SP1A-2)") (class "Default")
      (node (ref "SP-1") (pin "1") (pinfunction "1_1") (pintype "passive"))
      (node (ref "SP1") (pin "P$M") (pinfunction "2_P$M") (pintype "passive"))
      (node (ref "U1") (pin "8") (pinfunction "OUT-_8") (pintype "bidirectional"))
    )
    (net (code "72") (name "Net-(SP2A-1)") (class "Default")
      (node (ref "R17") (pin "2") (pinfunction "2_2") (pintype "passive"))
      (node (ref "SP+") (pin "1") (pinfunction "1_1") (pintype "passive"))
      (node (ref "SP2") (pin "P$P") (pinfunction "1_P$P") (pintype "passive"))
      (node (ref "U6") (pin "5") (pinfunction "OUT+_5") (pintype "bidirectional"))
    )
    (net (code "73") (name "Net-(SP2A-2)") (class "Default")
      (node (ref "SP-") (pin "1") (pinfunction "1_1") (pintype "passive"))
      (node (ref "SP2") (pin "P$M") (pinfunction "2_P$M") (pintype "passive"))
      (node (ref "U6") (pin "8") (pinfunction "OUT-_8") (pintype "bidirectional"))
    )
    (net (code "74") (name "Net-(U1-BIAS)") (class "Default")
      (node (ref "C25") (pin "1") (pinfunction "1_1") (pintype "passive"))
      (node (ref "U1") (pin "2") (pinfunction "BIAS_2") (pintype "bidirectional"))
      (node (ref "U1") (pin "3") (pinfunction "IN+_3") (pintype "bidirectional"))
    )
    (net (code "75") (name "Net-(U1-IN-)") (class "Default")
      (node (ref "R1") (pin "2") (pinfunction "2_2") (pintype "passive"))
      (node (ref "R2") (pin "1") (pinfunction "1_1") (pintype "passive"))
      (node (ref "U1") (pin "4") (pinfunction "IN-_4") (pintype "bidirectional"))
    )
    (net (code "76") (name "Net-(U6-BIAS)") (class "Default")
      (node (ref "C39") (pin "1") (pinfunction "1_1") (pintype "passive"))
      (node (ref "U6") (pin "2") (pinfunction "BIAS_2") (pintype "bidirectional"))
      (node (ref "U6") (pin "3") (pinfunction "IN+_3") (pintype "bidirectional"))
    )
    (net (code "77") (name "Net-(U6-IN-)") (class "Default")
      (node (ref "R17") (pin "1") (pinfunction "1_1") (pintype "passive"))
      (node (ref "R20") (pin "2") (pinfunction "2_2") (pintype "passive"))
      (node (ref "U6") (pin "4") (pinfunction "IN-_4") (pintype "bidirectional"))
    )
    (net (code "78") (name "unconnected-(J7-PadGNDBREAK)") (class "Default")
      (node (ref "J7") (pin "GNDBREAK") (pinfunction "GNDBREAK_GNDBREAK") (pintype "bidirectional"))
    )
  )
)
